# SCH_Infotiv_2023-08-07.net
KiCad netlist of a schematic drawn in EasyEDA
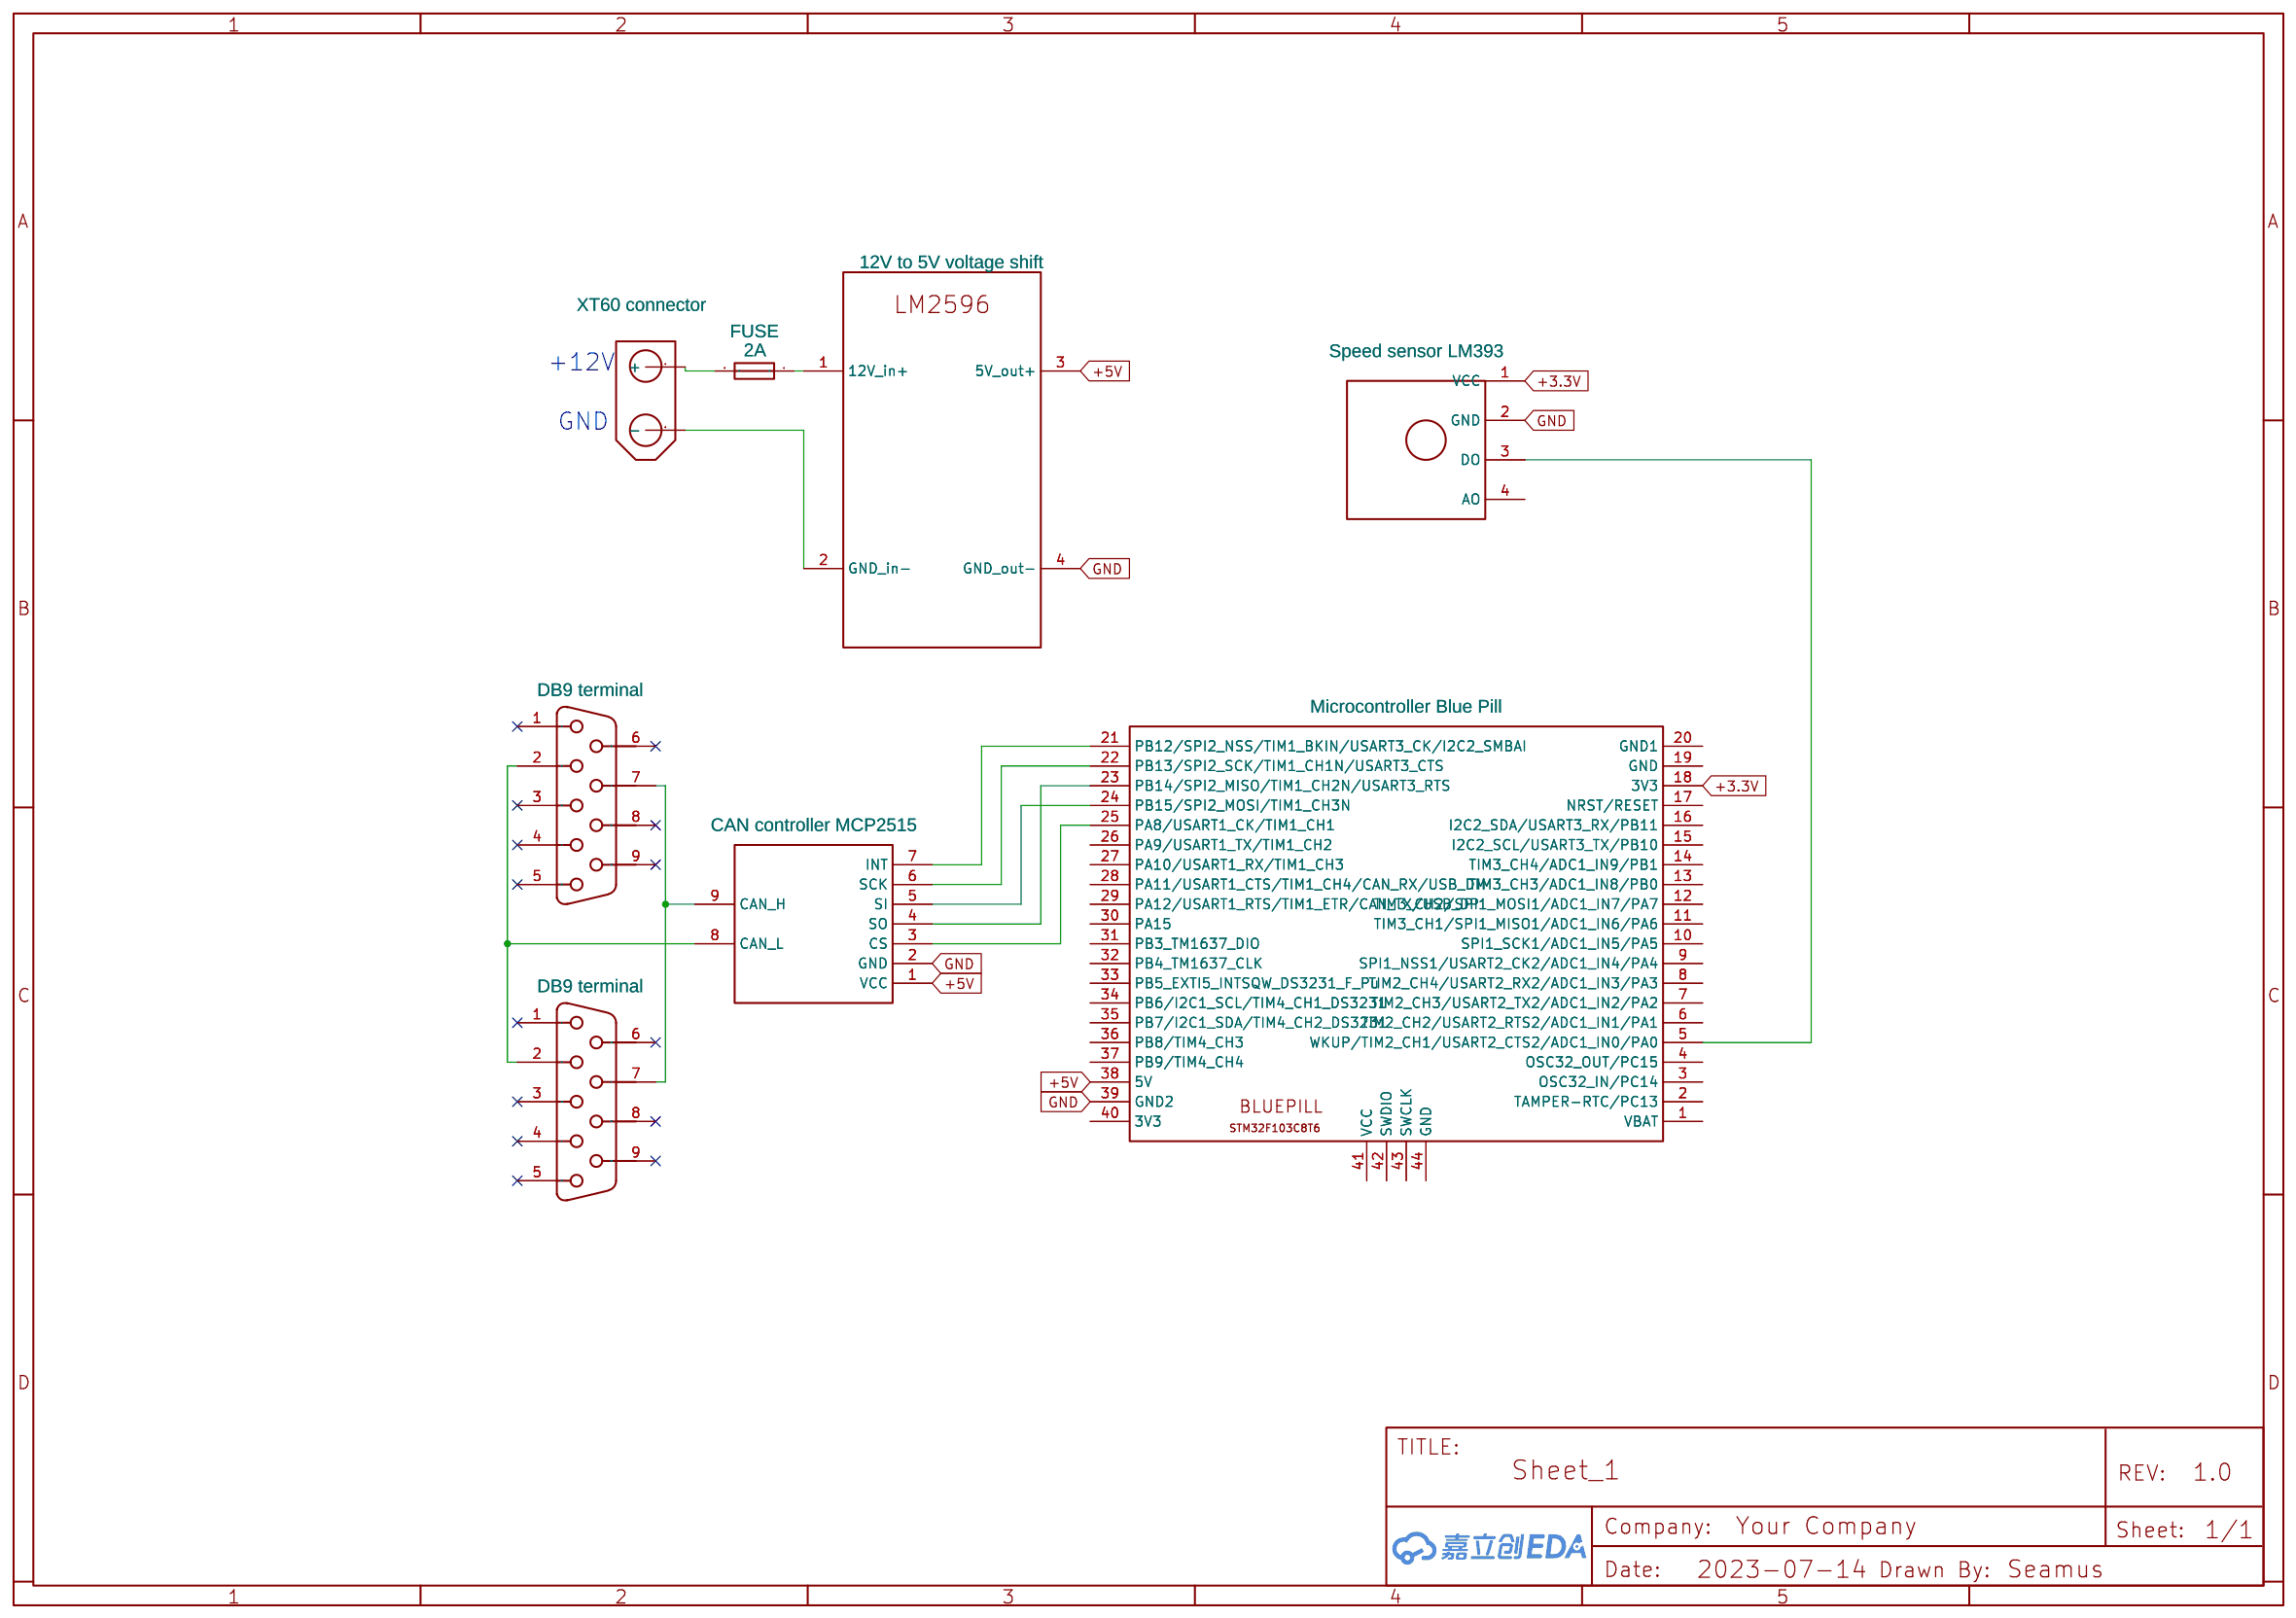
[diagram p0: schematic sheet]

(export (version "E")
  (design (tool "Eeschema 10.0.6"))
  (components
    (comp (ref "CN1")
      (value "XT60 connector")
      (fields
        (field (name "Manufacturer Part") "XT60PWE")
        (field (name "Manufacturer") "Changzhou Amass Elec")
      )
      (libsource (lib "") (part "XT60PWE"))
    )
    (comp (ref "FUSE")
      (value "2A")
      (fields (field (name "Manufacturer Part") "0448008.MR") (field (name "Manufacturer") "Littelfuse"))
      (libsource (lib "") (part "0448008.MR"))
    )
    (comp (ref "U2") (value "CAN controller MCP2515") (libsource (lib "") (part "MCP2515 COPY")))
    (comp (ref "U3")
      (value "12V to 5V voltage shift")
      (fields (field (name "Manufacturer Part") "LM2596"))
      (libsource (lib "") (part "LM2596"))
    )
    (comp (ref "U4") (value "Speed sensor LM393") (libsource (lib "") (part "LM393-MODULE-4PIN (JPAP)")))
    (comp (ref "U5") (value "Microcontroller Blue Pill") (libsource (lib "") (part "My_BluePill_2")))
    (comp (ref "U8")
      (value "DB9 terminal")
      (fields (field (name "Manufacturer Part") "DB9SS 直插公座"))
      (libsource (lib "") (part "DB9 female"))
    )
    (comp (ref "U9")
      (value "DB9 terminal")
      (fields (field (name "Manufacturer Part") "DB9SS 直插公座"))
      (libsource (lib "") (part "DB9 female"))
    )
  )
  (nets
    (net (code "1") (name "+3.3V") (class "Default")
      (node (ref "U4") (pin "1") (pinfunction "VCC_1") (pintype "unspecified"))
      (node (ref "U5") (pin "18") (pinfunction "3V3_18") (pintype "unspecified"))
    )
    (net (code "2") (name "+5V") (class "Default")
      (node (ref "U2") (pin "1") (pinfunction "VCC_1") (pintype "unspecified"))
      (node (ref "U3") (pin "3") (pinfunction "5V_out+_3") (pintype "unspecified"))
      (node (ref "U5") (pin "38") (pinfunction "5V_38") (pintype "unspecified"))
    )
    (net (code "3") (name "GND") (class "Default")
      (node (ref "U2") (pin "2") (pinfunction "GND_2") (pintype "unspecified"))
      (node (ref "U3") (pin "4") (pinfunction "GND_out-_4") (pintype "unspecified"))
      (node (ref "U4") (pin "2") (pinfunction "GND_2") (pintype "unspecified"))
      (node (ref "U5") (pin "39") (pinfunction "GND2_39") (pintype "unspecified"))
    )
    (net (code "4") (name "Net-(CN1-+)") (class "Default")
      (node (ref "CN1") (pin "1") (pinfunction "+_1") (pintype "unspecified"))
      (node (ref "FUSE") (pin "2") (pinfunction "2_2") (pintype "unspecified"))
    )
    (net (code "5") (name "Net-(CN1--)") (class "Default")
      (node (ref "CN1") (pin "2") (pinfunction "-_2") (pintype "unspecified"))
      (node (ref "U3") (pin "2") (pinfunction "GND_in-_2") (pintype "unspecified"))
    )
    (net (code "6") (name "Net-(U2-CAN_H)") (class "Default")
      (node (ref "U2") (pin "9") (pinfunction "CAN_H_9") (pintype "unspecified"))
      (node (ref "U8") (pin "7") (pinfunction "7_7") (pintype "input"))
      (node (ref "U9") (pin "7") (pinfunction "7_7") (pintype "input"))
    )
    (net (code "7") (name "Net-(U2-CAN_L)") (class "Default")
      (node (ref "U2") (pin "8") (pinfunction "CAN_L_8") (pintype "unspecified"))
      (node (ref "U8") (pin "2") (pinfunction "2_2") (pintype "input"))
      (node (ref "U9") (pin "2") (pinfunction "2_2") (pintype "input"))
    )
    (net (code "8") (name "Net-(U2-CS)") (class "Default")
      (node (ref "U2") (pin "3") (pinfunction "CS_3") (pintype "unspecified"))
      (node (ref "U5") (pin "25") (pinfunction "PA8/USART1_CK/TIM1_CH1_25") (pintype "unspecified"))
    )
    (net (code "9") (name "Net-(U2-INT)") (class "Default")
      (node (ref "U2") (pin "7") (pinfunction "INT_7") (pintype "unspecified"))
      (node (ref "U5") (pin "21") (pinfunction "PB12/SPI2_NSS/TIM1_BKIN/USART3_CK/I2C2_SMBAI_21") (pintype "unspecified"))
    )
    (net (code "10") (name "Net-(U2-SCK)") (class "Default")
      (node (ref "U2") (pin "6") (pinfunction "SCK_6") (pintype "unspecified"))
      (node (ref "U5") (pin "22") (pinfunction "PB13/SPI2_SCK/TIM1_CH1N/USART3_CTS_22") (pintype "unspecified"))
    )
    (net (code "11") (name "Net-(U2-SI)") (class "Default")
      (node (ref "U2") (pin "5") (pinfunction "SI_5") (pintype "unspecified"))
      (node (ref "U5") (pin "24") (pinfunction "PB15/SPI2_MOSI/TIM1_CH3N_24") (pintype "unspecified"))
    )
    (net (code "12") (name "Net-(U2-SO)") (class "Default")
      (node (ref "U2") (pin "4") (pinfunction "SO_4") (pintype "unspecified"))
      (node (ref "U5") (pin "23") (pinfunction "PB14/SPI2_MISO/TIM1_CH2N/USART3_RTS_23") (pintype "unspecified"))
    )
    (net (code "13") (name "Net-(U3-12V_in+)") (class "Default")
      (node (ref "FUSE") (pin "1") (pinfunction "1_1") (pintype "unspecified"))
      (node (ref "U3") (pin "1") (pinfunction "12V_in+_1") (pintype "unspecified"))
    )
    (net (code "14") (name "Net-(U4-DO)") (class "Default")
      (node (ref "U4") (pin "3") (pinfunction "DO_3") (pintype "unspecified"))
      (node (ref "U5") (pin "5") (pinfunction "WKUP/TIM2_CH1/USART2_CTS2/ADC1_IN0/PA0_5") (pintype "unspecified"))
    )
    (net (code "15") (name "unconnected-(U4-AO-Pad4)") (class "Default")
      (node (ref "U4") (pin "4") (pinfunction "AO_4") (pintype "unspecified"))
    )
    (net (code "16") (name "unconnected-(U5-3V3-Pad40)") (class "Default")
      (node (ref "U5") (pin "40") (pinfunction "3V3_40") (pintype "unspecified"))
    )
    (net (code "17") (name "unconnected-(U5-GND-Pad19)") (class "Default")
      (node (ref "U5") (pin "19") (pinfunction "GND_19") (pintype "unspecified"))
    )
    (net (code "18") (name "unconnected-(U5-GND-Pad44)") (class "Default")
      (node (ref "U5") (pin "44") (pinfunction "GND_44") (pintype "unspecified"))
    )
    (net (code "19") (name "unconnected-(U5-GND1-Pad20)") (class "Default")
      (node (ref "U5") (pin "20") (pinfunction "GND1_20") (pintype "unspecified"))
    )
    (net (code "20") (name "unconnected-(U5-I2C2_SCL{slash}USART3_TX{slash}PB10-Pad15)") (class "Default")
      (node (ref "U5") (pin "15") (pinfunction "I2C2_SCL/USART3_TX/PB10_15") (pintype "unspecified"))
    )
    (net (code "21") (name "unconnected-(U5-I2C2_SDA{slash}USART3_RX{slash}PB11-Pad16)") (class "Default")
      (node (ref "U5") (pin "16") (pinfunction "I2C2_SDA/USART3_RX/PB11_16") (pintype "unspecified"))
    )
    (net (code "22") (name "unconnected-(U5-NRST{slash}RESET-Pad17)") (class "Default")
      (node (ref "U5") (pin "17") (pinfunction "NRST/RESET_17") (pintype "unspecified"))
    )
    (net (code "23") (name "unconnected-(U5-OSC32_IN{slash}PC14-Pad3)") (class "Default")
      (node (ref "U5") (pin "3") (pinfunction "OSC32_IN/PC14_3") (pintype "unspecified"))
    )
    (net (code "24") (name "unconnected-(U5-OSC32_OUT{slash}PC15-Pad4)") (class "Default")
      (node (ref "U5") (pin "4") (pinfunction "OSC32_OUT/PC15_4") (pintype "unspecified"))
    )
    (net (code "25") (name "unconnected-(U5-PA9{slash}USART1_TX{slash}TIM1_CH2-Pad26)") (class "Default")
      (node (ref "U5") (pin "26") (pinfunction "PA9/USART1_TX/TIM1_CH2_26") (pintype "unspecified"))
    )
    (net (code "26") (name "unconnected-(U5-PA10{slash}USART1_RX{slash}TIM1_CH3-Pad27)") (class "Default")
      (node (ref "U5") (pin "27") (pinfunction "PA10/USART1_RX/TIM1_CH3_27") (pintype "unspecified"))
    )
    (net (code "27") (name "unconnected-(U5-PA11{slash}USART1_CTS{slash}TIM1_CH4{slash}CAN_RX{slash}USB_DM-Pad28)") (class "Default")
      (node (ref "U5") (pin "28") (pinfunction "PA11/USART1_CTS/TIM1_CH4/CAN_RX/USB_DM_28") (pintype "unspecified"))
    )
    (net (code "28") (name "unconnected-(U5-PA12{slash}USART1_RTS{slash}TIM1_ETR{slash}CAN_TX{slash}USB_DP-Pad29)") (class "Default")
      (node (ref "U5") (pin "29") (pinfunction "PA12/USART1_RTS/TIM1_ETR/CAN_TX/USB_DP_29") (pintype "unspecified"))
    )
    (net (code "29") (name "unconnected-(U5-PA15-Pad30)") (class "Default")
      (node (ref "U5") (pin "30") (pinfunction "PA15_30") (pintype "unspecified"))
    )
    (net (code "30") (name "unconnected-(U5-PB3_TM1637_DIO-Pad31)") (class "Default")
      (node (ref "U5") (pin "31") (pinfunction "PB3_TM1637_DIO_31") (pintype "unspecified"))
    )
    (net (code "31") (name "unconnected-(U5-PB4_TM1637_CLK-Pad32)") (class "Default")
      (node (ref "U5") (pin "32") (pinfunction "PB4_TM1637_CLK_32") (pintype "unspecified"))
    )
    (net (code "32") (name "unconnected-(U5-PB5_EXTI5_INTSQW_DS3231_F_Pu-Pad33)") (class "Default")
      (node (ref "U5") (pin "33") (pinfunction "PB5_EXTI5_INTSQW_DS3231_F_Pu_33") (pintype "unspecified"))
    )
    (net (code "33") (name "unconnected-(U5-PB6{slash}I2C1_SCL{slash}TIM4_CH1_DS3231-Pad34)") (class "Default")
      (node (ref "U5") (pin "34") (pinfunction "PB6/I2C1_SCL/TIM4_CH1_DS3231_34") (pintype "unspecified"))
    )
    (net (code "34") (name "unconnected-(U5-PB7{slash}I2C1_SDA{slash}TIM4_CH2_DS3231-Pad35)") (class "Default")
      (node (ref "U5") (pin "35") (pinfunction "PB7/I2C1_SDA/TIM4_CH2_DS3231_35") (pintype "unspecified"))
    )
    (net (code "35") (name "unconnected-(U5-PB8{slash}TIM4_CH3-Pad36)") (class "Default")
      (node (ref "U5") (pin "36") (pinfunction "PB8/TIM4_CH3_36") (pintype "unspecified"))
    )
    (net (code "36") (name "unconnected-(U5-PB9{slash}TIM4_CH4-Pad37)") (class "Default")
      (node (ref "U5") (pin "37") (pinfunction "PB9/TIM4_CH4_37") (pintype "unspecified"))
    )
    (net (code "37") (name "unconnected-(U5-SPI1_NSS1{slash}USART2_CK2{slash}ADC1_IN4{slash}PA4-Pad9)") (class "Default")
      (node (ref "U5") (pin "9") (pinfunction "SPI1_NSS1/USART2_CK2/ADC1_IN4/PA4_9") (pintype "unspecified"))
    )
    (net (code "38") (name "unconnected-(U5-SPI1_SCK1{slash}ADC1_IN5{slash}PA5-Pad10)") (class "Default")
      (node (ref "U5") (pin "10") (pinfunction "SPI1_SCK1/ADC1_IN5/PA5_10") (pintype "unspecified"))
    )
    (net (code "39") (name "unconnected-(U5-SWCLK-Pad43)") (class "Default")
      (node (ref "U5") (pin "43") (pinfunction "SWCLK_43") (pintype "unspecified"))
    )
    (net (code "40") (name "unconnected-(U5-SWDIO-Pad42)") (class "Default")
      (node (ref "U5") (pin "42") (pinfunction "SWDIO_42") (pintype "unspecified"))
    )
    (net (code "41") (name "unconnected-(U5-TAMPER-RTC{slash}PC13-Pad2)") (class "Default")
      (node (ref "U5") (pin "2") (pinfunction "TAMPER-RTC/PC13_2") (pintype "unspecified"))
    )
    (net (code "42") (name "unconnected-(U5-TIM2_CH2{slash}USART2_RTS2{slash}ADC1_IN1{slash}PA1-Pad6)") (class "Default")
      (node (ref "U5") (pin "6") (pinfunction "TIM2_CH2/USART2_RTS2/ADC1_IN1/PA1_6") (pintype "unspecified"))
    )
    (net (code "43") (name "unconnected-(U5-TIM2_CH3{slash}USART2_TX2{slash}ADC1_IN2{slash}PA2-Pad7)") (class "Default")
      (node (ref "U5") (pin "7") (pinfunction "TIM2_CH3/USART2_TX2/ADC1_IN2/PA2_7") (pintype "unspecified"))
    )
    (net (code "44") (name "unconnected-(U5-TIM2_CH4{slash}USART2_RX2{slash}ADC1_IN3{slash}PA3-Pad8)") (class "Default")
      (node (ref "U5") (pin "8") (pinfunction "TIM2_CH4/USART2_RX2/ADC1_IN3/PA3_8") (pintype "unspecified"))
    )
    (net (code "45") (name "unconnected-(U5-TIM3_CH1{slash}SPI1_MISO1{slash}ADC1_IN6{slash}PA6-Pad11)") (class "Default")
      (node (ref "U5") (pin "11") (pinfunction "TIM3_CH1/SPI1_MISO1/ADC1_IN6/PA6_11") (pintype "unspecified"))
    )
    (net (code "46") (name "unconnected-(U5-TIM3_CH2{slash}SPI1_MOSI1{slash}ADC1_IN7{slash}PA7-Pad12)") (class "Default")
      (node (ref "U5") (pin "12") (pinfunction "TIM3_CH2/SPI1_MOSI1/ADC1_IN7/PA7_12") (pintype "unspecified"))
    )
    (net (code "47") (name "unconnected-(U5-TIM3_CH3{slash}ADC1_IN8{slash}PB0-Pad13)") (class "Default")
      (node (ref "U5") (pin "13") (pinfunction "TIM3_CH3/ADC1_IN8/PB0_13") (pintype "unspecified"))
    )
    (net (code "48") (name "unconnected-(U5-TIM3_CH4{slash}ADC1_IN9{slash}PB1-Pad14)") (class "Default")
      (node (ref "U5") (pin "14") (pinfunction "TIM3_CH4/ADC1_IN9/PB1_14") (pintype "unspecified"))
    )
    (net (code "49") (name "unconnected-(U5-VBAT-Pad1)") (class "Default")
      (node (ref "U5") (pin "1") (pinfunction "VBAT_1") (pintype "unspecified"))
    )
    (net (code "50") (name "unconnected-(U5-VCC-Pad41)") (class "Default")
      (node (ref "U5") (pin "41") (pinfunction "VCC_41") (pintype "unspecified"))
    )
    (net (code "51") (name "unconnected-(U8-Pad1)") (class "Default")
      (node (ref "U8") (pin "1") (pinfunction "1_1") (pintype "input+no_connect"))
    )
    (net (code "52") (name "unconnected-(U8-Pad3)") (class "Default")
      (node (ref "U8") (pin "3") (pinfunction "3_3") (pintype "input+no_connect"))
    )
    (net (code "53") (name "unconnected-(U8-Pad4)") (class "Default")
      (node (ref "U8") (pin "4") (pinfunction "4_4") (pintype "input+no_connect"))
    )
    (net (code "54") (name "unconnected-(U8-Pad5)") (class "Default")
      (node (ref "U8") (pin "5") (pinfunction "5_5") (pintype "input+no_connect"))
    )
    (net (code "55") (name "unconnected-(U8-Pad6)") (class "Default")
      (node (ref "U8") (pin "6") (pinfunction "6_6") (pintype "input+no_connect"))
    )
    (net (code "56") (name "unconnected-(U8-Pad8)") (class "Default")
      (node (ref "U8") (pin "8") (pinfunction "8_8") (pintype "input+no_connect"))
    )
    (net (code "57") (name "unconnected-(U8-Pad9)") (class "Default")
      (node (ref "U8") (pin "9") (pinfunction "9_9") (pintype "input+no_connect"))
    )
    (net (code "58") (name "unconnected-(U9-Pad1)") (class "Default")
      (node (ref "U9") (pin "1") (pinfunction "1_1") (pintype "input+no_connect"))
    )
    (net (code "59") (name "unconnected-(U9-Pad3)") (class "Default")
      (node (ref "U9") (pin "3") (pinfunction "3_3") (pintype "input+no_connect"))
    )
    (net (code "60") (name "unconnected-(U9-Pad4)") (class "Default")
      (node (ref "U9") (pin "4") (pinfunction "4_4") (pintype "input+no_connect"))
    )
    (net (code "61") (name "unconnected-(U9-Pad5)") (class "Default")
      (node (ref "U9") (pin "5") (pinfunction "5_5") (pintype "input+no_connect"))
    )
    (net (code "62") (name "unconnected-(U9-Pad6)") (class "Default")
      (node (ref "U9") (pin "6") (pinfunction "6_6") (pintype "input+no_connect"))
    )
    (net (code "63") (name "unconnected-(U9-Pad8)") (class "Default")
      (node (ref "U9") (pin "8") (pinfunction "8_8") (pintype "input+no_connect"))
    )
    (net (code "64") (name "unconnected-(U9-Pad9)") (class "Default")
      (node (ref "U9") (pin "9") (pinfunction "9_9") (pintype "input+no_connect"))
    )
  )
)
